# GDT_Trafo.net
KiCad netlist of a schematic drawn in Altium Designer
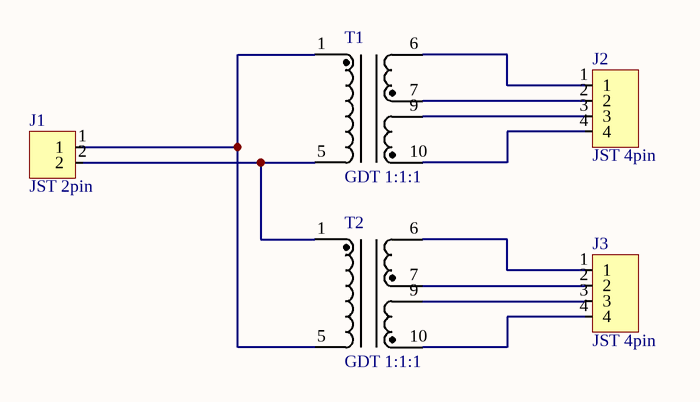
[diagram p0: GDT_Trafo.SchDoc]

(export (version "E")
  (design (tool "Eeschema 10.0.6"))
  (components
    (comp (ref "J1") (value "JST 2pin") (footprint "JST 2pin") (libsource (lib "Schlib1") (part "JST 2pin")))
    (comp (ref "J2") (value "JST 4pin") (footprint "JST 4pin") (libsource (lib "Schlib1") (part "JST 4pin")))
    (comp (ref "J3") (value "JST 4pin") (footprint "JST 4pin") (libsource (lib "Schlib1") (part "JST 4pin")))
    (comp (ref "T1")
      (value "GDT 1:1:1")
      (footprint "SD250-3")
      (libsource (lib "Schlib1") (part "GDT 1{colon}1{colon}1"))
    )
    (comp (ref "T2")
      (value "GDT 1:1:1")
      (footprint "SD250-3")
      (libsource (lib "Schlib1") (part "GDT 1{colon}1{colon}1"))
    )
  )
  (nets
    (net (code "1") (name "Net-(J1-Pad1)") (class "Default")
      (node (ref "J1") (pin "1") (pinfunction "1_1") (pintype "passive"))
      (node (ref "T1") (pin "1") (pinfunction "1_1") (pintype "passive"))
      (node (ref "T2") (pin "5") (pinfunction "5_5") (pintype "passive"))
    )
    (net (code "2") (name "Net-(J1-Pad2)") (class "Default")
      (node (ref "J1") (pin "2") (pinfunction "2_2") (pintype "passive"))
      (node (ref "T1") (pin "5") (pinfunction "5_5") (pintype "passive"))
      (node (ref "T2") (pin "1") (pinfunction "1_1") (pintype "passive"))
    )
    (net (code "3") (name "Net-(J2-Pad1)") (class "Default")
      (node (ref "J2") (pin "1") (pinfunction "1_1") (pintype "passive"))
      (node (ref "T1") (pin "6") (pinfunction "6_6") (pintype "passive"))
    )
    (net (code "4") (name "Net-(J2-Pad2)") (class "Default")
      (node (ref "J2") (pin "2") (pinfunction "2_2") (pintype "passive"))
      (node (ref "T1") (pin "7") (pinfunction "7_7") (pintype "passive"))
    )
    (net (code "5") (name "Net-(J2-Pad3)") (class "Default")
      (node (ref "J2") (pin "3") (pinfunction "3_3") (pintype "passive"))
      (node (ref "T1") (pin "9") (pinfunction "9_9") (pintype "passive"))
    )
    (net (code "6") (name "Net-(J2-Pad4)") (class "Default")
      (node (ref "J2") (pin "4") (pinfunction "4_4") (pintype "passive"))
      (node (ref "T1") (pin "10") (pinfunction "10_10") (pintype "passive"))
    )
    (net (code "7") (name "Net-(J3-Pad1)") (class "Default")
      (node (ref "J3") (pin "1") (pinfunction "1_1") (pintype "passive"))
      (node (ref "T2") (pin "6") (pinfunction "6_6") (pintype "passive"))
    )
    (net (code "8") (name "Net-(J3-Pad2)") (class "Default")
      (node (ref "J3") (pin "2") (pinfunction "2_2") (pintype "passive"))
      (node (ref "T2") (pin "7") (pinfunction "7_7") (pintype "passive"))
    )
    (net (code "9") (name "Net-(J3-Pad3)") (class "Default")
      (node (ref "J3") (pin "3") (pinfunction "3_3") (pintype "passive"))
      (node (ref "T2") (pin "9") (pinfunction "9_9") (pintype "passive"))
    )
    (net (code "10") (name "Net-(J3-Pad4)") (class "Default")
      (node (ref "J3") (pin "4") (pinfunction "4_4") (pintype "passive"))
      (node (ref "T2") (pin "10") (pinfunction "10_10") (pintype "passive"))
    )
  )
)
